# design.net
KiCad netlist of a schematic drawn in Altium Designer
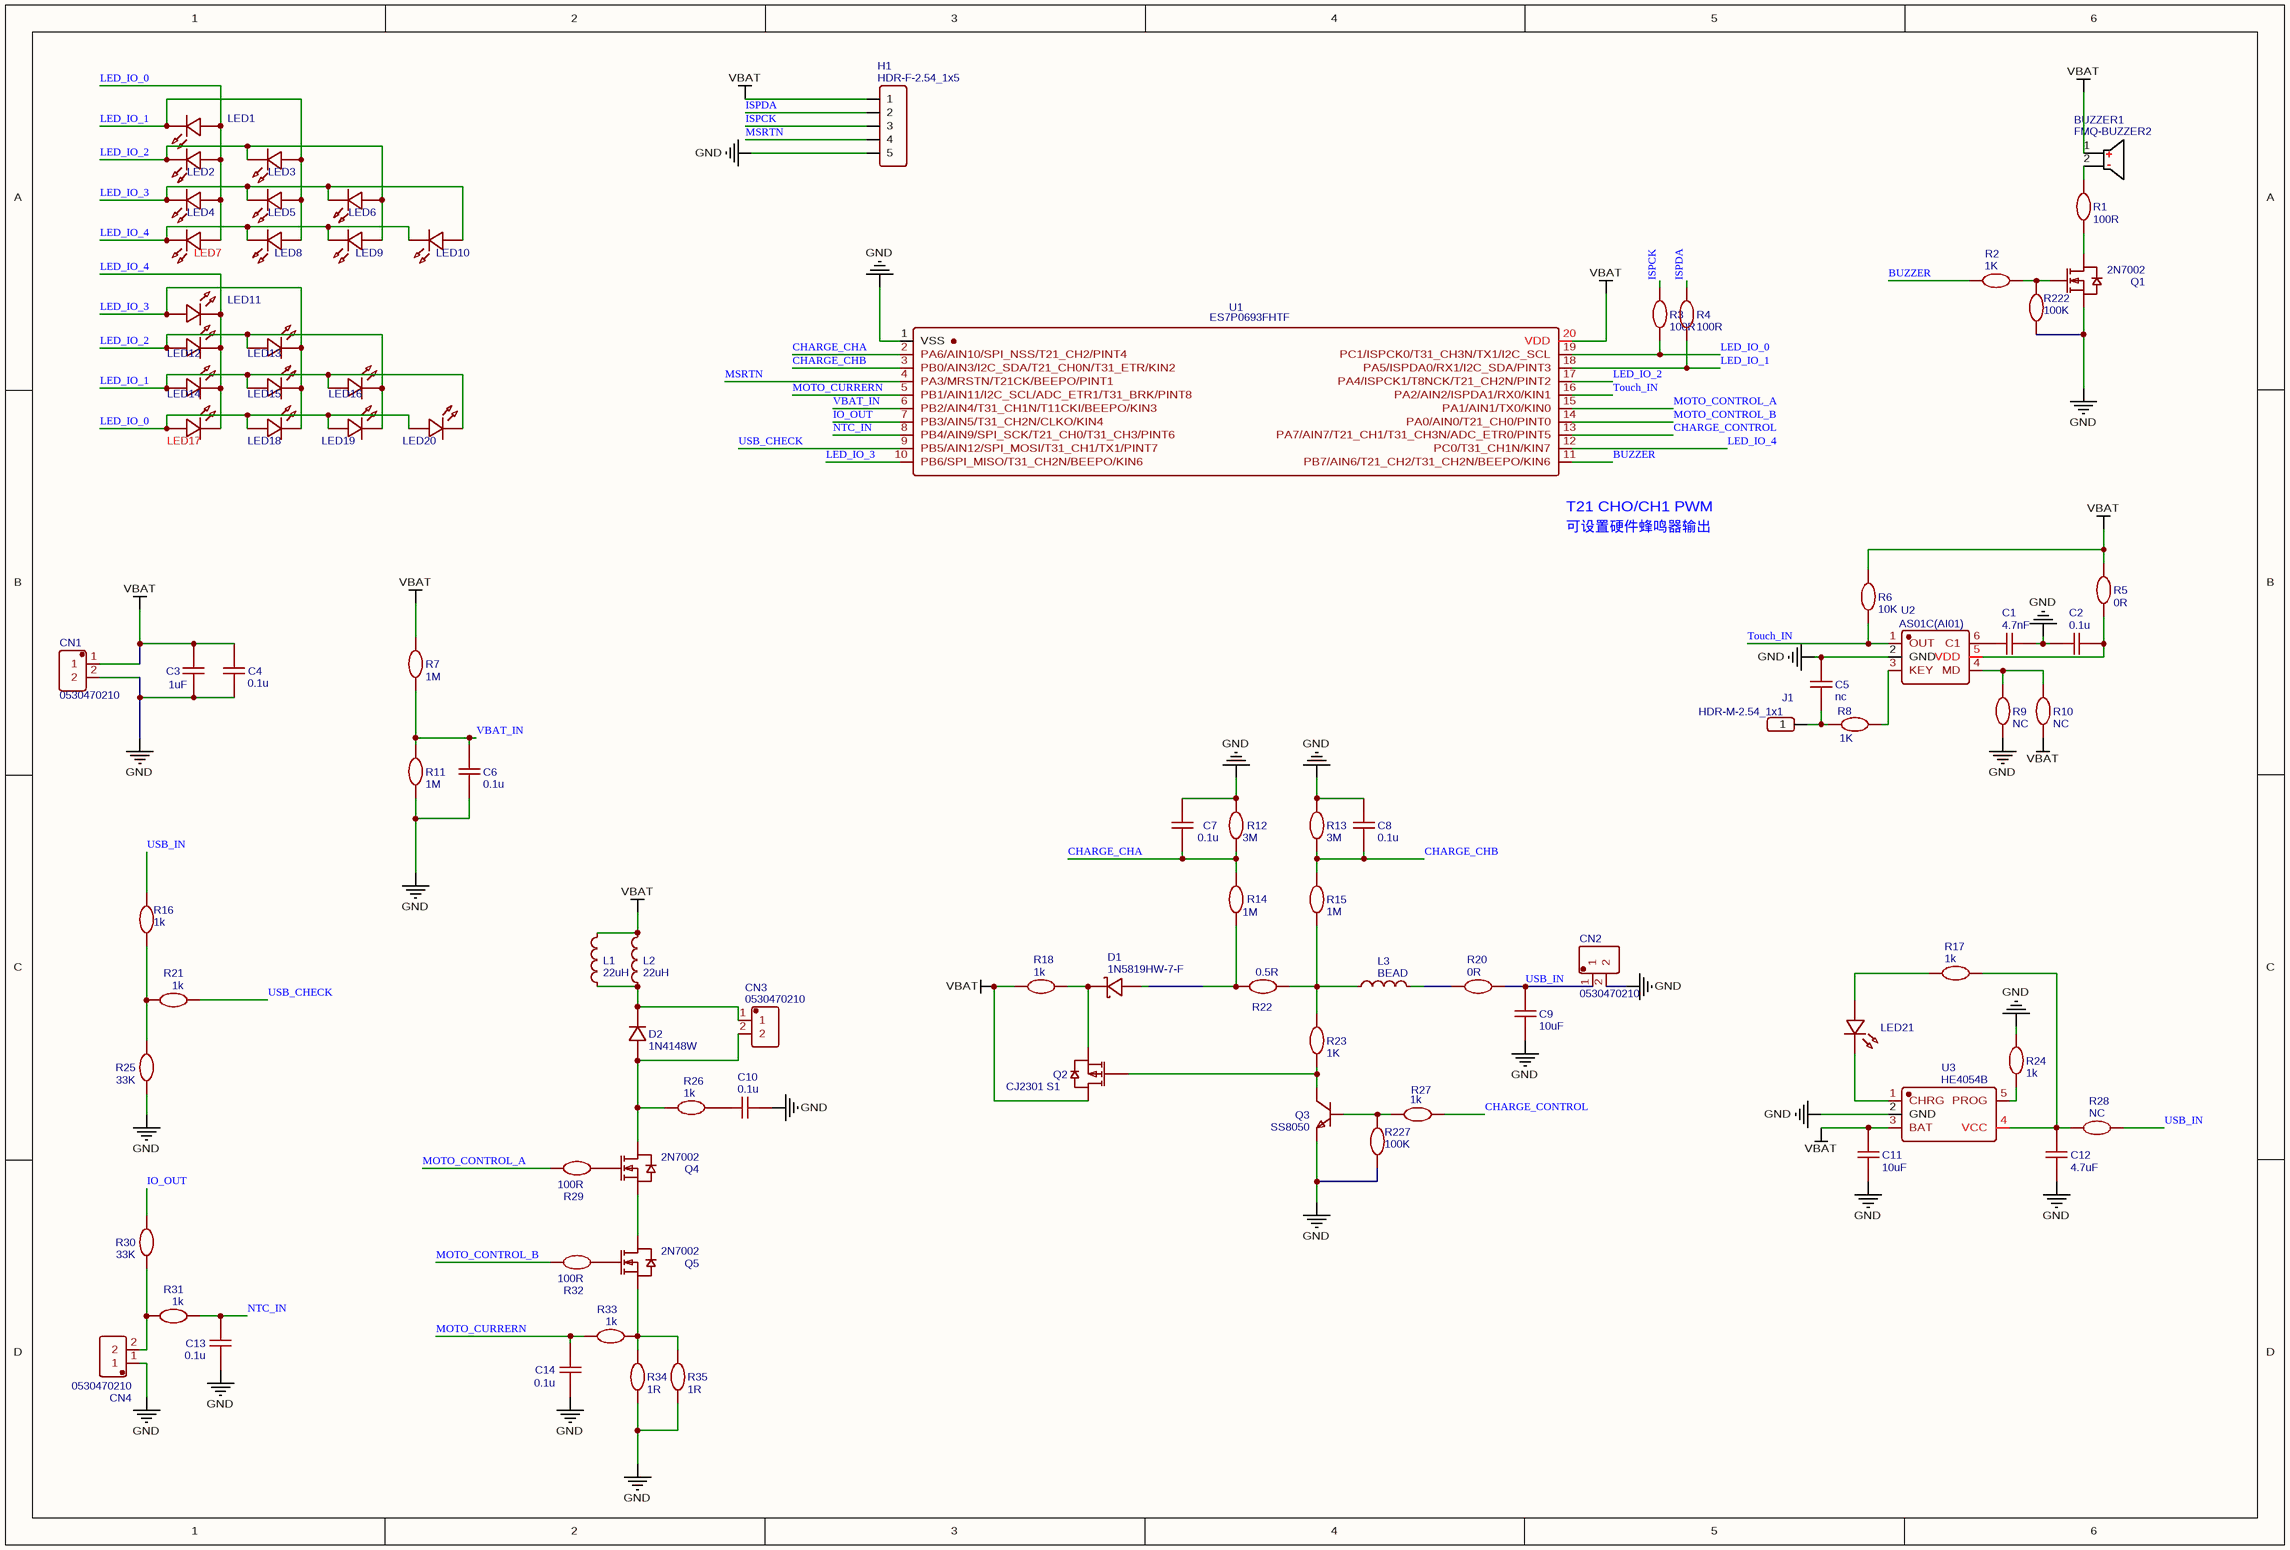
[diagram p0: 搅拌杯原理图.schdoc]

(export (version "E")
  (design (tool "Eeschema 10.0.6"))
  (components
    (comp (ref "BUZZER1")
      (value "FMQ-BUZZER2")
      (footprint "BUZ-TH_BD12.0-P7.60-D0.6-FD")
      (fields (field (name "BOM_SUPPLIER PART") "C9900006103") (field (name "CONTRIBUTOR") "LCSC"))
      (libsource (lib "altium-import") (part "root_0_FMQ-BUZZER2_"))
    )
    (comp (ref "C1")
      (value "4.7nF")
      (footprint "C0603")
      (fields (field (name "CONTRIBUTOR") "LCEDA_Lib"))
      (libsource (lib "altium-import") (part "root_0_4.7nF_"))
    )
    (comp (ref "C2")
      (value "0.1u")
      (footprint "C0603")
      (fields (field (name "CONTRIBUTOR") "LCEDA_Lib"))
      (libsource (lib "altium-import") (part "root_0_0.1u_"))
    )
    (comp (ref "C3")
      (value "1uF")
      (footprint "C0603")
      (fields (field (name "CONTRIBUTOR") "LCEDA_Lib"))
      (libsource (lib "altium-import") (part "root_3_1uF_"))
    )
    (comp (ref "C4")
      (value "0.1u")
      (footprint "C0603")
      (fields (field (name "CONTRIBUTOR") "LCEDA_Lib"))
      (libsource (lib "") (part "root_3_0.1u__1"))
    )
    (comp (ref "C5")
      (value "nc")
      (footprint "C0603")
      (fields (field (name "CONTRIBUTOR") "LCEDA_Lib"))
      (libsource (lib "altium-import") (part "root_1_nc_"))
    )
    (comp (ref "C6")
      (value "0.1u")
      (footprint "C0603")
      (fields (field (name "CONTRIBUTOR") "LCEDA_Lib"))
      (libsource (lib "altium-import") (part "root_1_0.1u_"))
    )
    (comp (ref "C7")
      (value "0.1u")
      (footprint "C0603")
      (fields (field (name "CONTRIBUTOR") "LCEDA_Lib"))
      (libsource (lib "altium-import") (part "root_3_0.1u_"))
    )
    (comp (ref "C8")
      (value "0.1u")
      (footprint "C0603")
      (fields (field (name "CONTRIBUTOR") "LCEDA_Lib"))
      (libsource (lib "altium-import") (part "root_1_0.1u_"))
    )
    (comp (ref "C9")
      (value "10uF")
      (footprint "C0603")
      (fields (field (name "CONTRIBUTOR") "LCEDA_Lib"))
      (libsource (lib "altium-import") (part "root_1_10uF_"))
    )
    (comp (ref "C10")
      (value "0.1u")
      (footprint "C0603")
      (fields (field (name "CONTRIBUTOR") "LCEDA_Lib"))
      (libsource (lib "altium-import") (part "root_2_0.1u_"))
    )
    (comp (ref "C11")
      (value "10uF")
      (footprint "C0603")
      (fields (field (name "CONTRIBUTOR") "LCEDA_Lib"))
      (libsource (lib "altium-import") (part "root_1_10uF_"))
    )
    (comp (ref "C12")
      (value "4.7uF")
      (footprint "C0603")
      (fields (field (name "CONTRIBUTOR") "LCEDA_Lib"))
      (libsource (lib "altium-import") (part "root_1_4.7uF_"))
    )
    (comp (ref "C13")
      (value "0.1u")
      (footprint "C0603")
      (fields (field (name "CONTRIBUTOR") "LCEDA_Lib"))
      (libsource (lib "altium-import") (part "root_3_0.1u_"))
    )
    (comp (ref "C14")
      (value "0.1u")
      (footprint "C0603")
      (fields (field (name "CONTRIBUTOR") "LCEDA_Lib"))
      (libsource (lib "") (part "root_1_0.1u__1"))
    )
    (comp (ref "CN1")
      (value "0530470210")
      (footprint "CONN-TH_0530470210")
      (fields (field (name "BOM_SUPPLIER PART") "C114130") (field (name "CONTRIBUTOR") "LCSC"))
      (libsource (lib "altium-import") (part "root_0_mirrored_0530470210_"))
    )
    (comp (ref "CN2")
      (value "0530470210")
      (footprint "CONN-TH_0530470210")
      (fields (field (name "BOM_SUPPLIER PART") "C114130") (field (name "CONTRIBUTOR") "LCSC"))
      (libsource (lib "altium-import") (part "root_1_mirrored_0530470210_"))
    )
    (comp (ref "CN3")
      (value "0530470210")
      (footprint "CONN-TH_0530470210")
      (fields (field (name "BOM_SUPPLIER PART") "C114130") (field (name "CONTRIBUTOR") "LCSC"))
      (libsource (lib "altium-import") (part "root_0_0530470210_"))
    )
    (comp (ref "CN4")
      (value "0530470210")
      (footprint "CONN-TH_0530470210")
      (fields (field (name "BOM_SUPPLIER PART") "C114130") (field (name "CONTRIBUTOR") "LCSC"))
      (libsource (lib "") (part "root_0_0530470210__1"))
    )
    (comp (ref "D1")
      (value "1N5819HW-7-F")
      (footprint "SOD-123_L2.8-W1.8-LS3.7-FD")
      (fields (field (name "BOM_SUPPLIER PART") "C82544"))
      (libsource (lib "altium-import") (part "root_2_1N5819HW-7-F_"))
    )
    (comp (ref "D2")
      (value "1N4148W")
      (footprint "SOD-123FL_L2.6-W1.6-LS3.4-RD")
      (fields (field (name "BOM_SUPPLIER PART") "C129216") (field (name "CONTRIBUTOR") "LCEDA_Lib"))
      (libsource (lib "altium-import") (part "root_1_1N4148W_"))
    )
    (comp (ref "H1")
      (value "HDR-F-2.54_1x5")
      (footprint "1.27mm_5PIN")
      (fields (field (name "BOM_SUPPLIER PART") "C50950") (field (name "CONTRIBUTOR") "LCEDA_Lib"))
      (libsource (lib "altium-import") (part "root_0_HDR-F-2.54_1x5_"))
    )
    (comp (ref "J1")
      (value "HDR-M-2.54_1x1")
      (footprint "HDR-M-2.54_1X1")
      (fields (field (name "BOM_SUPPLIER PART") "C81276") (field (name "CONTRIBUTOR") "LCEDA_Lib"))
      (libsource (lib "altium-import") (part "root_2_HDR-M-2.54_1x1_"))
    )
    (comp (ref "L1")
      (value "22uH")
      (footprint "L0603")
      (fields (field (name "CONTRIBUTOR") "LCEDA_Lib"))
      (libsource (lib "altium-import") (part "root_1_22uH_"))
    )
    (comp (ref "L2")
      (value "22uH")
      (footprint "L0603")
      (fields (field (name "CONTRIBUTOR") "LCEDA_Lib"))
      (libsource (lib "altium-import") (part "root_1_22uH_"))
    )
    (comp (ref "L3")
      (value "BEAD")
      (footprint "L0603")
      (fields (field (name "CONTRIBUTOR") "LCEDA_Lib"))
      (libsource (lib "altium-import") (part "root_0_22uH_"))
    )
    (comp (ref "LED1")
      (value "LED-0603_W")
      (footprint "LED0603-FD_WHITE")
      (fields
        (field (name "BOM_MANUFACTURER PART") "17-21SURC/S530-A3/TR8")
        (field (name "BOM_SUPPLIER PART") "C72037")
        (field (name "CONTRIBUTOR") "LCEDA_Lib")
      )
      (libsource (lib "altium-import") (part "root_2_LED-0603_W_"))
    )
    (comp (ref "LED2")
      (value "LED-0603_W")
      (footprint "LED0603-FD_WHITE")
      (fields
        (field (name "BOM_MANUFACTURER PART") "17-21SURC/S530-A3/TR8")
        (field (name "BOM_SUPPLIER PART") "C72037")
        (field (name "CONTRIBUTOR") "LCEDA_Lib")
      )
      (libsource (lib "altium-import") (part "root_2_LED-0603_W_"))
    )
    (comp (ref "LED3")
      (value "LED-0603_W")
      (footprint "LED0603-FD_WHITE")
      (fields
        (field (name "BOM_MANUFACTURER PART") "17-21SURC/S530-A3/TR8")
        (field (name "BOM_SUPPLIER PART") "C72037")
        (field (name "CONTRIBUTOR") "LCEDA_Lib")
      )
      (libsource (lib "altium-import") (part "root_2_LED-0603_W_"))
    )
    (comp (ref "LED4")
      (value "LED-0603_W")
      (footprint "LED0603-FD_WHITE")
      (fields
        (field (name "BOM_MANUFACTURER PART") "17-21SURC/S530-A3/TR8")
        (field (name "BOM_SUPPLIER PART") "C72037")
        (field (name "CONTRIBUTOR") "LCEDA_Lib")
      )
      (libsource (lib "altium-import") (part "root_2_LED-0603_W_"))
    )
    (comp (ref "LED5")
      (value "LED-0603_W")
      (footprint "LED0603-FD_WHITE")
      (fields
        (field (name "BOM_MANUFACTURER PART") "17-21SURC/S530-A3/TR8")
        (field (name "BOM_SUPPLIER PART") "C72037")
        (field (name "CONTRIBUTOR") "LCEDA_Lib")
      )
      (libsource (lib "altium-import") (part "root_2_LED-0603_W_"))
    )
    (comp (ref "LED6")
      (value "LED-0603_W")
      (footprint "LED0603-FD_WHITE")
      (fields
        (field (name "BOM_MANUFACTURER PART") "17-21SURC/S530-A3/TR8")
        (field (name "BOM_SUPPLIER PART") "C72037")
        (field (name "CONTRIBUTOR") "LCEDA_Lib")
      )
      (libsource (lib "altium-import") (part "root_2_LED-0603_W_"))
    )
    (comp (ref "LED7")
      (value "LED-0603_W")
      (footprint "LED0603-FD_WHITE")
      (fields
        (field (name "BOM_MANUFACTURER PART") "17-21SURC/S530-A3/TR8")
        (field (name "BOM_SUPPLIER PART") "C72037")
        (field (name "CONTRIBUTOR") "LCEDA_Lib")
      )
      (libsource (lib "altium-import") (part "root_2_LED-0603_W_"))
    )
    (comp (ref "LED8")
      (value "LED-0603_W")
      (footprint "LED0603-FD_WHITE")
      (fields
        (field (name "BOM_MANUFACTURER PART") "17-21SURC/S530-A3/TR8")
        (field (name "BOM_SUPPLIER PART") "C72037")
        (field (name "CONTRIBUTOR") "LCEDA_Lib")
      )
      (libsource (lib "altium-import") (part "root_2_LED-0603_W_"))
    )
    (comp (ref "LED9")
      (value "LED-0603_W")
      (footprint "LED0603-FD_WHITE")
      (fields
        (field (name "BOM_MANUFACTURER PART") "17-21SURC/S530-A3/TR8")
        (field (name "BOM_SUPPLIER PART") "C72037")
        (field (name "CONTRIBUTOR") "LCEDA_Lib")
      )
      (libsource (lib "altium-import") (part "root_2_LED-0603_W_"))
    )
    (comp (ref "LED10")
      (value "LED-0603_W")
      (footprint "LED0603-FD_WHITE")
      (fields
        (field (name "BOM_MANUFACTURER PART") "17-21SURC/S530-A3/TR8")
        (field (name "BOM_SUPPLIER PART") "C72037")
        (field (name "CONTRIBUTOR") "LCEDA_Lib")
      )
      (libsource (lib "altium-import") (part "root_2_LED-0603_W_"))
    )
    (comp (ref "LED11")
      (value "LED-0603_W")
      (footprint "LED0603-FD_WHITE")
      (fields
        (field (name "BOM_MANUFACTURER PART") "17-21SURC/S530-A3/TR8")
        (field (name "BOM_SUPPLIER PART") "C72037")
        (field (name "CONTRIBUTOR") "LCEDA_Lib")
      )
      (libsource (lib "altium-import") (part "root_0_LED-0603_W_"))
    )
    (comp (ref "LED12")
      (value "LED-0603_W")
      (footprint "LED0603-FD_WHITE")
      (fields
        (field (name "BOM_MANUFACTURER PART") "17-21SURC/S530-A3/TR8")
        (field (name "BOM_SUPPLIER PART") "C72037")
        (field (name "CONTRIBUTOR") "LCEDA_Lib")
      )
      (libsource (lib "altium-import") (part "root_0_LED-0603_W_"))
    )
    (comp (ref "LED13")
      (value "LED-0603_W")
      (footprint "LED0603-FD_WHITE")
      (fields
        (field (name "BOM_MANUFACTURER PART") "17-21SURC/S530-A3/TR8")
        (field (name "BOM_SUPPLIER PART") "C72037")
        (field (name "CONTRIBUTOR") "LCEDA_Lib")
      )
      (libsource (lib "altium-import") (part "root_0_LED-0603_W_"))
    )
    (comp (ref "LED14")
      (value "LED-0603_W")
      (footprint "LED0603-FD_WHITE")
      (fields
        (field (name "BOM_MANUFACTURER PART") "17-21SURC/S530-A3/TR8")
        (field (name "BOM_SUPPLIER PART") "C72037")
        (field (name "CONTRIBUTOR") "LCEDA_Lib")
      )
      (libsource (lib "altium-import") (part "root_0_LED-0603_W_"))
    )
    (comp (ref "LED15")
      (value "LED-0603_W")
      (footprint "LED0603-FD_WHITE")
      (fields
        (field (name "BOM_MANUFACTURER PART") "17-21SURC/S530-A3/TR8")
        (field (name "BOM_SUPPLIER PART") "C72037")
        (field (name "CONTRIBUTOR") "LCEDA_Lib")
      )
      (libsource (lib "altium-import") (part "root_0_LED-0603_W_"))
    )
    (comp (ref "LED16")
      (value "LED-0603_W")
      (footprint "LED0603-FD_WHITE")
      (fields
        (field (name "BOM_MANUFACTURER PART") "17-21SURC/S530-A3/TR8")
        (field (name "BOM_SUPPLIER PART") "C72037")
        (field (name "CONTRIBUTOR") "LCEDA_Lib")
      )
      (libsource (lib "altium-import") (part "root_0_LED-0603_W_"))
    )
    (comp (ref "LED17")
      (value "LED-0603_W")
      (footprint "LED0603-FD_WHITE")
      (fields
        (field (name "BOM_MANUFACTURER PART") "17-21SURC/S530-A3/TR8")
        (field (name "BOM_SUPPLIER PART") "C72037")
        (field (name "CONTRIBUTOR") "LCEDA_Lib")
      )
      (libsource (lib "altium-import") (part "root_0_LED-0603_W_"))
    )
    (comp (ref "LED18")
      (value "LED-0603_W")
      (footprint "LED0603-FD_WHITE")
      (fields
        (field (name "BOM_MANUFACTURER PART") "17-21SURC/S530-A3/TR8")
        (field (name "BOM_SUPPLIER PART") "C72037")
        (field (name "CONTRIBUTOR") "LCEDA_Lib")
      )
      (libsource (lib "altium-import") (part "root_0_LED-0603_W_"))
    )
    (comp (ref "LED19")
      (value "LED-0603_W")
      (footprint "LED0603-FD_WHITE")
      (fields
        (field (name "BOM_MANUFACTURER PART") "17-21SURC/S530-A3/TR8")
        (field (name "BOM_SUPPLIER PART") "C72037")
        (field (name "CONTRIBUTOR") "LCEDA_Lib")
      )
      (libsource (lib "altium-import") (part "root_0_LED-0603_W_"))
    )
    (comp (ref "LED20")
      (value "LED-0603_W")
      (footprint "LED0603-FD_WHITE")
      (fields
        (field (name "BOM_MANUFACTURER PART") "17-21SURC/S530-A3/TR8")
        (field (name "BOM_SUPPLIER PART") "C72037")
        (field (name "CONTRIBUTOR") "LCEDA_Lib")
      )
      (libsource (lib "altium-import") (part "root_0_LED-0603_W_"))
    )
    (comp (ref "LED21")
      (value "LED-0603_W")
      (footprint "LED0603-FD_WHITE")
      (fields
        (field (name "BOM_MANUFACTURER PART") "17-21SURC/S530-A3/TR8")
        (field (name "BOM_SUPPLIER PART") "C72037")
        (field (name "CONTRIBUTOR") "LCEDA_Lib")
      )
      (libsource (lib "altium-import") (part "root_3_LED-0603_W_"))
    )
    (comp (ref "Q1")
      (value "2N7002")
      (footprint "SOT-23_L2.9-W1.3-P0.95-LS2.4-BR")
      (fields
        (field (name "BOM_MANUFACTURER PART") "2N7002,215")
        (field (name "BOM_SUPPLIER PART") "C65189")
        (field (name "CONTRIBUTOR") "LCEDA_Lib")
      )
      (libsource (lib "altium-import") (part "root_2_2N7002_"))
    )
    (comp (ref "Q2")
      (value "CJ2301 S1")
      (footprint "SOT-23-3_L3.0-W1.7-P0.95-LS2.9-BR")
      (fields (field (name "BOM_SUPPLIER PART") "C8547"))
      (libsource (lib "altium-import") (part "root_2_CJ2301 S1_"))
    )
    (comp (ref "Q3")
      (value "SS8050")
      (footprint "SOT-23-3_L2.9-W1.3-P1.90-LS2.4-BR")
      (fields (field (name "BOM_SUPPLIER PART") "C908250") (field (name "CONTRIBUTOR") "LCSC"))
      (libsource (lib "altium-import") (part "root_0_SS8050_"))
    )
    (comp (ref "Q4")
      (value "2N7002")
      (footprint "SOT-23_L2.9-W1.3-P0.95-LS2.4-BR")
      (fields
        (field (name "BOM_MANUFACTURER PART") "2N7002,215")
        (field (name "BOM_SUPPLIER PART") "C65189")
        (field (name "CONTRIBUTOR") "LCEDA_Lib")
      )
      (libsource (lib "altium-import") (part "root_2_2N7002_"))
    )
    (comp (ref "Q5")
      (value "2N7002")
      (footprint "SOT-23_L2.9-W1.3-P0.95-LS2.4-BR")
      (fields
        (field (name "BOM_MANUFACTURER PART") "2N7002,215")
        (field (name "BOM_SUPPLIER PART") "C65189")
        (field (name "CONTRIBUTOR") "LCEDA_Lib")
      )
      (libsource (lib "altium-import") (part "root_2_2N7002_"))
    )
    (comp (ref "R1")
      (value "100R")
      (footprint "R0603")
      (fields (field (name "CONTRIBUTOR") "LCEDA_Lib"))
      (libsource (lib "altium-import") (part "root_3_100R_"))
    )
    (comp (ref "R2")
      (value "1K")
      (footprint "R0603")
      (fields (field (name "CONTRIBUTOR") "LCEDA_Lib"))
      (libsource (lib "altium-import") (part "root_2_1K_"))
    )
    (comp (ref "R3")
      (value "100R")
      (footprint "R0603")
      (fields (field (name "CONTRIBUTOR") "LCEDA_Lib"))
      (libsource (lib "altium-import") (part "root_3_100R_"))
    )
    (comp (ref "R4")
      (value "100R")
      (footprint "R0603")
      (fields (field (name "CONTRIBUTOR") "LCEDA_Lib"))
      (libsource (lib "altium-import") (part "root_3_100R_"))
    )
    (comp (ref "R5")
      (value "0R")
      (footprint "R0603")
      (fields (field (name "CONTRIBUTOR") "LCEDA_Lib"))
      (libsource (lib "altium-import") (part "root_1_NC_"))
    )
    (comp (ref "R6")
      (value "10K")
      (footprint "R0603")
      (fields (field (name "CONTRIBUTOR") "LCEDA_Lib"))
      (libsource (lib "altium-import") (part "root_1_NC_"))
    )
    (comp (ref "R7")
      (value "1M")
      (footprint "R0603")
      (fields (field (name "CONTRIBUTOR") "LCEDA_Lib"))
      (libsource (lib "altium-import") (part "root_1_430k_"))
    )
    (comp (ref "R8")
      (value "1K")
      (footprint "R0603")
      (fields (field (name "CONTRIBUTOR") "LCEDA_Lib"))
      (libsource (lib "altium-import") (part "root_2_1K_"))
    )
    (comp (ref "R9")
      (value "NC")
      (footprint "R0603")
      (fields (field (name "CONTRIBUTOR") "LCEDA_Lib"))
      (libsource (lib "altium-import") (part "root_1_NC_"))
    )
    (comp (ref "R10")
      (value "NC")
      (footprint "R0603")
      (fields (field (name "CONTRIBUTOR") "LCEDA_Lib"))
      (libsource (lib "altium-import") (part "root_1_NC_"))
    )
    (comp (ref "R11")
      (value "1M")
      (footprint "R0603")
      (fields (field (name "CONTRIBUTOR") "LCEDA_Lib"))
      (libsource (lib "altium-import") (part "root_1_430K_"))
    )
    (comp (ref "R12")
      (value "3M")
      (footprint "R0603")
      (fields (field (name "CONTRIBUTOR") "LCEDA_Lib"))
      (libsource (lib "") (part "root_3_1k__1"))
    )
    (comp (ref "R13")
      (value "3M")
      (footprint "R0603")
      (fields (field (name "CONTRIBUTOR") "LCEDA_Lib"))
      (libsource (lib "altium-import") (part "root_1_1k_"))
    )
    (comp (ref "R14")
      (value "1M")
      (footprint "R0603")
      (fields (field (name "CONTRIBUTOR") "LCEDA_Lib"))
      (libsource (lib "altium-import") (part "root_3_1k_"))
    )
    (comp (ref "R15")
      (value "1M")
      (footprint "R0603")
      (fields (field (name "CONTRIBUTOR") "LCEDA_Lib"))
      (libsource (lib "altium-import") (part "root_1_1k_"))
    )
    (comp (ref "R16")
      (value "1k")
      (footprint "R0603")
      (fields (field (name "CONTRIBUTOR") "LCEDA_Lib"))
      (libsource (lib "altium-import") (part "root_3_1k_"))
    )
    (comp (ref "R17")
      (value "1k")
      (footprint "R0603")
      (fields (field (name "CONTRIBUTOR") "LCEDA_Lib"))
      (libsource (lib "altium-import") (part "root_2_1k_"))
    )
    (comp (ref "R18")
      (value "1k")
      (footprint "R0603")
      (fields (field (name "CONTRIBUTOR") "LCEDA_Lib"))
      (libsource (lib "altium-import") (part "root_2_1k_"))
    )
    (comp (ref "R20")
      (value "0R")
      (footprint "R0603")
      (fields (field (name "CONTRIBUTOR") "LCEDA_Lib"))
      (libsource (lib "altium-import") (part "root_2_NC_"))
    )
    (comp (ref "R21")
      (value "1k")
      (footprint "R0603")
      (fields (field (name "CONTRIBUTOR") "LCEDA_Lib"))
      (libsource (lib "") (part "root_2_1k__1"))
    )
    (comp (ref "R22")
      (value "0.5R")
      (footprint "R1206")
      (fields (field (name "CONTRIBUTOR") "LCEDA_Lib"))
      (libsource (lib "altium-import") (part "root_0_0.5R_"))
    )
    (comp (ref "R23")
      (value "1K")
      (footprint "R0603")
      (fields (field (name "CONTRIBUTOR") "LCEDA_Lib"))
      (libsource (lib "altium-import") (part "root_1_1k_"))
    )
    (comp (ref "R24")
      (value "1k")
      (footprint "R0603")
      (fields (field (name "CONTRIBUTOR") "LCEDA_Lib"))
      (libsource (lib "altium-import") (part "root_1_1k_"))
    )
    (comp (ref "R25")
      (value "33K")
      (footprint "R0603")
      (fields (field (name "CONTRIBUTOR") "LCEDA_Lib"))
      (libsource (lib "altium-import") (part "root_3_33K_"))
    )
    (comp (ref "R26")
      (value "1k")
      (footprint "R0603")
      (fields (field (name "CONTRIBUTOR") "LCEDA_Lib"))
      (libsource (lib "altium-import") (part "root_2_1k_"))
    )
    (comp (ref "R27")
      (value "1k")
      (footprint "R0603")
      (fields (field (name "CONTRIBUTOR") "LCEDA_Lib"))
      (libsource (lib "") (part "root_0_1k__1"))
    )
    (comp (ref "R28")
      (value "NC")
      (footprint "R0603")
      (fields (field (name "CONTRIBUTOR") "LCEDA_Lib"))
      (libsource (lib "altium-import") (part "root_0_NC_"))
    )
    (comp (ref "R29")
      (value "100R")
      (footprint "R0603")
      (fields (field (name "CONTRIBUTOR") "LCEDA_Lib"))
      (libsource (lib "altium-import") (part "root_2_100R_"))
    )
    (comp (ref "R30")
      (value "33K")
      (footprint "R0603")
      (fields (field (name "CONTRIBUTOR") "LCEDA_Lib"))
      (libsource (lib "altium-import") (part "root_3_33K_"))
    )
    (comp (ref "R31")
      (value "1k")
      (footprint "R0603")
      (fields (field (name "CONTRIBUTOR") "LCEDA_Lib"))
      (libsource (lib "") (part "root_2_1k__1"))
    )
    (comp (ref "R32")
      (value "100R")
      (footprint "R0603")
      (fields (field (name "CONTRIBUTOR") "LCEDA_Lib"))
      (libsource (lib "altium-import") (part "root_2_100R_"))
    )
    (comp (ref "R33")
      (value "1k")
      (footprint "R0603")
      (fields (field (name "CONTRIBUTOR") "LCEDA_Lib"))
      (libsource (lib "altium-import") (part "root_0_1k_"))
    )
    (comp (ref "R34")
      (value "1R")
      (footprint "R1206")
      (fields (field (name "CONTRIBUTOR") "LCEDA_Lib"))
      (libsource (lib "altium-import") (part "root_1_1R_"))
    )
    (comp (ref "R35")
      (value "1R")
      (footprint "R1206")
      (fields (field (name "CONTRIBUTOR") "LCEDA_Lib"))
      (libsource (lib "altium-import") (part "root_1_1R_"))
    )
    (comp (ref "R222")
      (value "100K")
      (footprint "R0603")
      (fields (field (name "CONTRIBUTOR") "LCEDA_Lib"))
      (libsource (lib "altium-import") (part "root_3_1K_"))
    )
    (comp (ref "R227")
      (value "100K")
      (footprint "R0603")
      (fields (field (name "CONTRIBUTOR") "LCEDA_Lib"))
      (libsource (lib "altium-import") (part "root_3_1K_"))
    )
    (comp (ref "U1")
      (value "ES7P0693FHTF")
      (footprint "TSOP20")
      (fields (field (name "CONTRIBUTOR") "zime_zl"))
      (libsource (lib "altium-import") (part "root_0_ES7P0693FHTF_"))
    )
    (comp (ref "U2")
      (value "AS01C(AI01)")
      (footprint "SOT-23-6_L2.9-W1.6-P0.95-LS2.8-BL")
      (fields (field (name "BOM_SUPPLIER PART") "C389617") (field (name "CONTRIBUTOR") "LCSC"))
      (libsource (lib "altium-import") (part "root_0_AS01C(AI01)_"))
    )
    (comp (ref "U3")
      (value "HE4054B")
      (footprint "SOT-23-5_L3.0-W1.7-P0.95-LS2.8-BR")
      (fields (field (name "BOM_SUPPLIER PART") "C711953") (field (name "CONTRIBUTOR") "LCSC"))
      (libsource (lib "altium-import") (part "root_0_HE4054B_"))
    )
  )
  (nets
    (net (code "1") (name "/BUZZER") (class "Default")
      (node (ref "R2") (pin "2") (pinfunction "2_2") (pintype "passive"))
      (node (ref "U1") (pin "11") (pinfunction "PB7/AIN6/T21_CH2/T31_CH2N/BEEPO/KIN6_11") (pintype "passive"))
    )
    (net (code "2") (name "/CHARGE_CHA") (class "Default")
      (node (ref "C7") (pin "2") (pinfunction "2_2") (pintype "passive"))
      (node (ref "R12") (pin "2") (pinfunction "2_2") (pintype "passive"))
      (node (ref "R14") (pin "2") (pinfunction "2_2") (pintype "passive"))
      (node (ref "U1") (pin "2") (pinfunction "PA6/AIN10/SPI_NSS/T21_CH2/PINT4_2") (pintype "passive"))
    )
    (net (code "3") (name "/CHARGE_CHB") (class "Default")
      (node (ref "C8") (pin "1") (pinfunction "1_1") (pintype "passive"))
      (node (ref "R13") (pin "1") (pinfunction "1_1") (pintype "passive"))
      (node (ref "R15") (pin "2") (pinfunction "2_2") (pintype "passive"))
      (node (ref "U1") (pin "3") (pinfunction "PB0/AIN3/I2C_SDA/T21_CH0N/T31_ETR/KIN2_3") (pintype "passive"))
    )
    (net (code "4") (name "/CHARGE_CONTROL") (class "Default")
      (node (ref "R27") (pin "2") (pinfunction "2_2") (pintype "passive"))
      (node (ref "U1") (pin "13") (pinfunction "PA7/AIN7/T21_CH1/T31_CH3N/ADC_ETR0/PINT5_13") (pintype "passive"))
    )
    (net (code "5") (name "/IO_OUT") (class "Default")
      (node (ref "R30") (pin "1") (pinfunction "1_1") (pintype "passive"))
      (node (ref "U1") (pin "7") (pinfunction "PB3/AIN5/T31_CH2N/CLKO/KIN4_7") (pintype "passive"))
    )
    (net (code "6") (name "/ISPCK") (class "Default")
      (node (ref "H1") (pin "3") (pinfunction "3_3") (pintype "passive"))
      (node (ref "R3") (pin "1") (pinfunction "1_1") (pintype "passive"))
    )
    (net (code "7") (name "/ISPDA") (class "Default")
      (node (ref "H1") (pin "2") (pinfunction "2_2") (pintype "passive"))
      (node (ref "R4") (pin "1") (pinfunction "1_1") (pintype "passive"))
    )
    (net (code "8") (name "/LED_IO_0") (class "Default")
      (node (ref "LED1") (pin "1") (pinfunction "1_1") (pintype "passive"))
      (node (ref "LED17") (pin "1") (pinfunction "1_1") (pintype "passive"))
      (node (ref "LED18") (pin "1") (pinfunction "1_1") (pintype "passive"))
      (node (ref "LED19") (pin "1") (pinfunction "1_1") (pintype "passive"))
      (node (ref "LED2") (pin "1") (pinfunction "1_1") (pintype "passive"))
      (node (ref "LED20") (pin "1") (pinfunction "1_1") (pintype "passive"))
      (node (ref "LED4") (pin "1") (pinfunction "1_1") (pintype "passive"))
      (node (ref "LED7") (pin "1") (pinfunction "1_1") (pintype "passive"))
      (node (ref "R3") (pin "2") (pinfunction "2_2") (pintype "passive"))
      (node (ref "U1") (pin "19") (pinfunction "PC1/ISPCK0/T31_CH3N/TX1/I2C_SCL_19") (pintype "passive"))
    )
    (net (code "9") (name "/LED_IO_1") (class "Default")
      (node (ref "LED1") (pin "2") (pinfunction "2_2") (pintype "passive"))
      (node (ref "LED14") (pin "1") (pinfunction "1_1") (pintype "passive"))
      (node (ref "LED15") (pin "1") (pinfunction "1_1") (pintype "passive"))
      (node (ref "LED16") (pin "1") (pinfunction "1_1") (pintype "passive"))
      (node (ref "LED20") (pin "2") (pinfunction "2_2") (pintype "passive"))
      (node (ref "LED3") (pin "1") (pinfunction "1_1") (pintype "passive"))
      (node (ref "LED5") (pin "1") (pinfunction "1_1") (pintype "passive"))
      (node (ref "LED8") (pin "1") (pinfunction "1_1") (pintype "passive"))
      (node (ref "R4") (pin "2") (pinfunction "2_2") (pintype "passive"))
      (node (ref "U1") (pin "18") (pinfunction "PA5/ISPDA0/RX1/I2C_SDA/PINT3_18") (pintype "passive"))
    )
    (net (code "10") (name "/LED_IO_2") (class "Default")
      (node (ref "LED12") (pin "1") (pinfunction "1_1") (pintype "passive"))
      (node (ref "LED13") (pin "1") (pinfunction "1_1") (pintype "passive"))
      (node (ref "LED16") (pin "2") (pinfunction "2_2") (pintype "passive"))
      (node (ref "LED19") (pin "2") (pinfunction "2_2") (pintype "passive"))
      (node (ref "LED2") (pin "2") (pinfunction "2_2") (pintype "passive"))
      (node (ref "LED3") (pin "2") (pinfunction "2_2") (pintype "passive"))
      (node (ref "LED6") (pin "1") (pinfunction "1_1") (pintype "passive"))
      (node (ref "LED9") (pin "1") (pinfunction "1_1") (pintype "passive"))
      (node (ref "U1") (pin "17") (pinfunction "PA4/ISPCK1/T8NCK/T21_CH2N/PINT2_17") (pintype "passive"))
    )
    (net (code "11") (name "/LED_IO_3") (class "Default")
      (node (ref "LED10") (pin "1") (pinfunction "1_1") (pintype "passive"))
      (node (ref "LED11") (pin "1") (pinfunction "1_1") (pintype "passive"))
      (node (ref "LED13") (pin "2") (pinfunction "2_2") (pintype "passive"))
      (node (ref "LED15") (pin "2") (pinfunction "2_2") (pintype "passive"))
      (node (ref "LED18") (pin "2") (pinfunction "2_2") (pintype "passive"))
      (node (ref "LED4") (pin "2") (pinfunction "2_2") (pintype "passive"))
      (node (ref "LED5") (pin "2") (pinfunction "2_2") (pintype "passive"))
      (node (ref "LED6") (pin "2") (pinfunction "2_2") (pintype "passive"))
      (node (ref "U1") (pin "10") (pinfunction "PB6/SPI_MISO/T31_CH2N/BEEPO/KIN6_10") (pintype "passive"))
    )
    (net (code "12") (name "/LED_IO_4") (class "Default")
      (node (ref "LED10") (pin "2") (pinfunction "2_2") (pintype "passive"))
      (node (ref "LED11") (pin "2") (pinfunction "2_2") (pintype "passive"))
      (node (ref "LED12") (pin "2") (pinfunction "2_2") (pintype "passive"))
      (node (ref "LED14") (pin "2") (pinfunction "2_2") (pintype "passive"))
      (node (ref "LED17") (pin "2") (pinfunction "2_2") (pintype "passive"))
      (node (ref "LED7") (pin "2") (pinfunction "2_2") (pintype "passive"))
      (node (ref "LED8") (pin "2") (pinfunction "2_2") (pintype "passive"))
      (node (ref "LED9") (pin "2") (pinfunction "2_2") (pintype "passive"))
      (node (ref "U1") (pin "12") (pinfunction "PC0/T31_CH1N/KIN7_12") (pintype "passive"))
    )
    (net (code "13") (name "/MOTO_CONTROL_A") (class "Default")
      (node (ref "R29") (pin "1") (pinfunction "1_1") (pintype "passive"))
      (node (ref "U1") (pin "15") (pinfunction "PA1/AIN1/TX0/KIN0_15") (pintype "passive"))
    )
    (net (code "14") (name "/MOTO_CONTROL_B") (class "Default")
      (node (ref "R32") (pin "1") (pinfunction "1_1") (pintype "passive"))
      (node (ref "U1") (pin "14") (pinfunction "PA0/AIN0/T21_CH0/PINT0_14") (pintype "passive"))
    )
    (net (code "15") (name "/MOTO_CURRERN") (class "Default")
      (node (ref "C14") (pin "2") (pinfunction "2_2") (pintype "passive"))
      (node (ref "R33") (pin "2") (pinfunction "2_2") (pintype "passive"))
      (node (ref "U1") (pin "5") (pinfunction "PB1/AIN11/I2C_SCL/ADC_ETR1/T31_BRK/PINT8_5") (pintype "passive"))
    )
    (net (code "16") (name "/MSRTN") (class "Default")
      (node (ref "H1") (pin "4") (pinfunction "4_4") (pintype "passive"))
      (node (ref "U1") (pin "4") (pinfunction "PA3/MRSTN/T21CK/BEEPO/PINT1_4") (pintype "passive"))
    )
    (net (code "17") (name "/NTC_IN") (class "Default")
      (node (ref "C13") (pin "1") (pinfunction "1_1") (pintype "passive"))
      (node (ref "R31") (pin "2") (pinfunction "2_2") (pintype "passive"))
      (node (ref "U1") (pin "8") (pinfunction "PB4/AIN9/SPI_SCK/T21_CH0/T31_CH3/PINT6_8") (pintype "passive"))
    )
    (net (code "18") (name "/Touch_IN") (class "Default")
      (node (ref "R6") (pin "1") (pinfunction "1_1") (pintype "passive"))
      (node (ref "U1") (pin "16") (pinfunction "PA2/AIN2/ISPDA1/RX0/KIN1_16") (pintype "passive"))
      (node (ref "U2") (pin "1") (pinfunction "OUT_1") (pintype "passive"))
    )
    (net (code "19") (name "/USB_CHECK") (class "Default")
      (node (ref "R21") (pin "2") (pinfunction "2_2") (pintype "passive"))
      (node (ref "U1") (pin "9") (pinfunction "PB5/AIN12/SPI_MOSI/T31_CH1/TX1/PINT7_9") (pintype "passive"))
    )
    (net (code "20") (name "/USB_IN") (class "Default")
      (node (ref "C9") (pin "2") (pinfunction "2_2") (pintype "passive"))
      (node (ref "CN2") (pin "1") (pinfunction "1_1") (pintype "passive"))
      (node (ref "R16") (pin "2") (pinfunction "2_2") (pintype "passive"))
      (node (ref "R20") (pin "1") (pinfunction "1_1") (pintype "passive"))
      (node (ref "R28") (pin "2") (pinfunction "2_2") (pintype "passive"))
    )
    (net (code "21") (name "/VBAT_IN") (class "Default")
      (node (ref "C6") (pin "2") (pinfunction "2_2") (pintype "passive"))
      (node (ref "R11") (pin "2") (pinfunction "2_2") (pintype "passive"))
      (node (ref "R7") (pin "1") (pinfunction "1_1") (pintype "passive"))
      (node (ref "U1") (pin "6") (pinfunction "PB2/AIN4/T31_CH1N/T11CKI/BEEPO/KIN3_6") (pintype "passive"))
    )
    (net (code "22") (name "GND") (class "Default")
      (node (ref "C1") (pin "2") (pinfunction "2_2") (pintype "passive"))
      (node (ref "C10") (pin "1") (pinfunction "1_1") (pintype "passive"))
      (node (ref "C11") (pin "1") (pinfunction "1_1") (pintype "passive"))
      (node (ref "C12") (pin "1") (pinfunction "1_1") (pintype "passive"))
      (node (ref "C13") (pin "2") (pinfunction "2_2") (pintype "passive"))
      (node (ref "C14") (pin "1") (pinfunction "1_1") (pintype "passive"))
      (node (ref "C2") (pin "1") (pinfunction "1_1") (pintype "passive"))
      (node (ref "C3") (pin "2") (pinfunction "2_2") (pintype "passive"))
      (node (ref "C4") (pin "2") (pinfunction "2_2") (pintype "passive"))
      (node (ref "C5") (pin "2") (pinfunction "2_2") (pintype "passive"))
      (node (ref "C6") (pin "1") (pinfunction "1_1") (pintype "passive"))
      (node (ref "C7") (pin "1") (pinfunction "1_1") (pintype "passive"))
      (node (ref "C8") (pin "2") (pinfunction "2_2") (pintype "passive"))
      (node (ref "C9") (pin "1") (pinfunction "1_1") (pintype "passive"))
      (node (ref "CN1") (pin "2") (pinfunction "2_2") (pintype "passive"))
      (node (ref "CN2") (pin "2") (pinfunction "2_2") (pintype "passive"))
      (node (ref "CN4") (pin "1") (pinfunction "1_1") (pintype "passive"))
      (node (ref "H1") (pin "5") (pinfunction "5_5") (pintype "passive"))
      (node (ref "Q1") (pin "2") (pinfunction "S_2") (pintype "passive"))
      (node (ref "Q3") (pin "2") (pinfunction "E_2") (pintype "passive"))
      (node (ref "R11") (pin "1") (pinfunction "1_1") (pintype "passive"))
      (node (ref "R12") (pin "1") (pinfunction "1_1") (pintype "passive"))
      (node (ref "R13") (pin "2") (pinfunction "2_2") (pintype "passive"))
      (node (ref "R222") (pin "2") (pinfunction "2_2") (pintype "passive"))
      (node (ref "R227") (pin "2") (pinfunction "2_2") (pintype "passive"))
      (node (ref "R24") (pin "2") (pinfunction "2_2") (pintype "passive"))
      (node (ref "R25") (pin "2") (pinfunction "2_2") (pintype "passive"))
      (node (ref "R34") (pin "1") (pinfunction "1_1") (pintype "passive"))
      (node (ref "R35") (pin "1") (pinfunction "1_1") (pintype "passive"))
      (node (ref "R9") (pin "1") (pinfunction "1_1") (pintype "passive"))
      (node (ref "U1") (pin "1") (pinfunction "VSS_1") (pintype "passive"))
      (node (ref "U2") (pin "2") (pinfunction "GND_2") (pintype "passive"))
      (node (ref "U3") (pin "2") (pinfunction "GND_2") (pintype "passive"))
    )
    (net (code "23") (name "Net-(BUZZER1-Pad2)") (class "Default")
      (node (ref "BUZZER1") (pin "2") (pinfunction "2_2") (pintype "passive"))
      (node (ref "R1") (pin "1") (pinfunction "1_1") (pintype "passive"))
    )
    (net (code "24") (name "Net-(C5-Pad1)") (class "Default")
      (node (ref "C5") (pin "1") (pinfunction "1_1") (pintype "passive"))
      (node (ref "J1") (pin "1") (pinfunction "1_1") (pintype "passive"))
      (node (ref "R8") (pin "2") (pinfunction "2_2") (pintype "passive"))
    )
    (net (code "25") (name "Net-(C10-Pad2)") (class "Default")
      (node (ref "C10") (pin "2") (pinfunction "2_2") (pintype "passive"))
      (node (ref "R26") (pin "1") (pinfunction "1_1") (pintype "passive"))
    )
    (net (code "26") (name "Net-(CN3-Pad1)") (class "Default")
      (node (ref "CN3") (pin "1") (pinfunction "1_1") (pintype "passive"))
      (node (ref "D2") (pin "1") (pinfunction "1_1") (pintype "passive"))
      (node (ref "L1") (pin "1") (pinfunction "1_1") (pintype "passive"))
      (node (ref "L2") (pin "1") (pinfunction "1_1") (pintype "passive"))
    )
    (net (code "27") (name "Net-(CN4-Pad2)") (class "Default")
      (node (ref "CN4") (pin "2") (pinfunction "2_2") (pintype "passive"))
      (node (ref "R30") (pin "2") (pinfunction "2_2") (pintype "passive"))
      (node (ref "R31") (pin "1") (pinfunction "1_1") (pintype "passive"))
    )
    (net (code "28") (name "Net-(D1-A)") (class "Default")
      (node (ref "D1") (pin "1") (pinfunction "A_1") (pintype "passive"))
      (node (ref "R14") (pin "1") (pinfunction "1_1") (pintype "passive"))
      (node (ref "R22") (pin "1") (pinfunction "1_1") (pintype "passive"))
    )
    (net (code "29") (name "Net-(D1-K)") (class "Default")
      (node (ref "D1") (pin "2") (pinfunction "K_2") (pintype "passive"))
      (node (ref "Q2") (pin "2") (pinfunction "S_2") (pintype "passive"))
      (node (ref "R18") (pin "1") (pinfunction "1_1") (pintype "passive"))
    )
    (net (code "30") (name "Net-(L3-Pad1)") (class "Default")
      (node (ref "L3") (pin "1") (pinfunction "1_1") (pintype "passive"))
      (node (ref "R15") (pin "1") (pinfunction "1_1") (pintype "passive"))
      (node (ref "R22") (pin "2") (pinfunction "2_2") (pintype "passive"))
      (node (ref "R23") (pin "2") (pinfunction "2_2") (pintype "passive"))
    )
    (net (code "31") (name "Net-(L3-Pad2)") (class "Default")
      (node (ref "L3") (pin "2") (pinfunction "2_2") (pintype "passive"))
      (node (ref "R20") (pin "2") (pinfunction "2_2") (pintype "passive"))
    )
    (net (code "32") (name "Net-(LED21-Pad1)") (class "Default")
      (node (ref "LED21") (pin "1") (pinfunction "1_1") (pintype "passive"))
      (node (ref "R17") (pin "2") (pinfunction "2_2") (pintype "passive"))
    )
    (net (code "33") (name "Net-(Q1-D)") (class "Default")
      (node (ref "Q1") (pin "3") (pinfunction "D_3") (pintype "passive"))
      (node (ref "R1") (pin "2") (pinfunction "2_2") (pintype "passive"))
    )
    (net (code "34") (name "Net-(Q1-G)") (class "Default")
      (node (ref "Q1") (pin "1") (pinfunction "G_1") (pintype "passive"))
      (node (ref "R2") (pin "1") (pinfunction "1_1") (pintype "passive"))
      (node (ref "R222") (pin "1") (pinfunction "1_1") (pintype "passive"))
    )
    (net (code "35") (name "Net-(Q2-G)") (class "Default")
      (node (ref "Q2") (pin "1") (pinfunction "G_1") (pintype "passive"))
      (node (ref "Q3") (pin "3") (pinfunction "C_3") (pintype "passive"))
      (node (ref "R23") (pin "1") (pinfunction "1_1") (pintype "passive"))
    )
    (net (code "36") (name "Net-(Q3-B)") (class "Default")
      (node (ref "Q3") (pin "1") (pinfunction "B_1") (pintype "passive"))
      (node (ref "R227") (pin "1") (pinfunction "1_1") (pintype "passive"))
      (node (ref "R27") (pin "1") (pinfunction "1_1") (pintype "passive"))
    )
    (net (code "37") (name "Net-(Q4-D)") (class "Default")
      (node (ref "CN3") (pin "2") (pinfunction "2_2") (pintype "passive"))
      (node (ref "D2") (pin "2") (pinfunction "2_2") (pintype "passive"))
      (node (ref "Q4") (pin "3") (pinfunction "D_3") (pintype "passive"))
      (node (ref "R26") (pin "2") (pinfunction "2_2") (pintype "passive"))
    )
    (net (code "38") (name "Net-(Q4-G)") (class "Default")
      (node (ref "Q4") (pin "1") (pinfunction "G_1") (pintype "passive"))
      (node (ref "R29") (pin "2") (pinfunction "2_2") (pintype "passive"))
    )
    (net (code "39") (name "Net-(Q4-S)") (class "Default")
      (node (ref "Q4") (pin "2") (pinfunction "S_2") (pintype "passive"))
      (node (ref "Q5") (pin "3") (pinfunction "D_3") (pintype "passive"))
    )
    (net (code "40") (name "Net-(Q5-G)") (class "Default")
      (node (ref "Q5") (pin "1") (pinfunction "G_1") (pintype "passive"))
      (node (ref "R32") (pin "2") (pinfunction "2_2") (pintype "passive"))
    )
    (net (code "41") (name "Net-(Q5-S)") (class "Default")
      (node (ref "Q5") (pin "2") (pinfunction "S_2") (pintype "passive"))
      (node (ref "R33") (pin "1") (pinfunction "1_1") (pintype "passive"))
      (node (ref "R34") (pin "2") (pinfunction "2_2") (pintype "passive"))
      (node (ref "R35") (pin "2") (pinfunction "2_2") (pintype "passive"))
    )
    (net (code "42") (name "Net-(R16-Pad1)") (class "Default")
      (node (ref "R16") (pin "1") (pinfunction "1_1") (pintype "passive"))
      (node (ref "R21") (pin "1") (pinfunction "1_1") (pintype "passive"))
      (node (ref "R25") (pin "1") (pinfunction "1_1") (pintype "passive"))
    )
    (net (code "43") (name "Net-(U2-C1)") (class "Default")
      (node (ref "C1") (pin "1") (pinfunction "1_1") (pintype "passive"))
      (node (ref "U2") (pin "6") (pinfunction "C1_6") (pintype "passive"))
    )
    (net (code "44") (name "Net-(U2-KEY)") (class "Default")
      (node (ref "R8") (pin "1") (pinfunction "1_1") (pintype "passive"))
      (node (ref "U2") (pin "3") (pinfunction "KEY_3") (pintype "passive"))
    )
    (net (code "45") (name "Net-(U2-MD)") (class "Default")
      (node (ref "R10") (pin "2") (pinfunction "2_2") (pintype "passive"))
      (node (ref "R9") (pin "2") (pinfunction "2_2") (pintype "passive"))
      (node (ref "U2") (pin "4") (pinfunction "MD_4") (pintype "passive"))
    )
    (net (code "46") (name "Net-(U2-VDD)") (class "Default")
      (node (ref "C2") (pin "2") (pinfunction "2_2") (pintype "passive"))
      (node (ref "R5") (pin "1") (pinfunction "1_1") (pintype "passive"))
      (node (ref "U2") (pin "5") (pinfunction "VDD_5") (pintype "passive"))
    )
    (net (code "47") (name "Net-(U3-CHRG)") (class "Default")
      (node (ref "LED21") (pin "2") (pinfunction "2_2") (pintype "passive"))
      (node (ref "U3") (pin "1") (pinfunction "CHRG_1") (pintype "passive"))
    )
    (net (code "48") (name "Net-(U3-PROG)") (class "Default")
      (node (ref "R24") (pin "1") (pinfunction "1_1") (pintype "passive"))
      (node (ref "U3") (pin "5") (pinfunction "PROG_5") (pintype "passive"))
    )
    (net (code "49") (name "Net-(U3-VCC)") (class "Default")
      (node (ref "C12") (pin "2") (pinfunction "2_2") (pintype "passive"))
      (node (ref "R17") (pin "1") (pinfunction "1_1") (pintype "passive"))
      (node (ref "R28") (pin "1") (pinfunction "1_1") (pintype "passive"))
      (node (ref "U3") (pin "4") (pinfunction "VCC_4") (pintype "passive"))
    )
    (net (code "50") (name "VBAT") (class "Default")
      (node (ref "BUZZER1") (pin "1") (pinfunction "1_1") (pintype "passive"))
      (node (ref "C11") (pin "2") (pinfunction "2_2") (pintype "passive"))
      (node (ref "C3") (pin "1") (pinfunction "1_1") (pintype "passive"))
      (node (ref "C4") (pin "1") (pinfunction "1_1") (pintype "passive"))
      (node (ref "CN1") (pin "1") (pinfunction "1_1") (pintype "passive"))
      (node (ref "H1") (pin "1") (pinfunction "1_1") (pintype "passive"))
      (node (ref "L1") (pin "2") (pinfunction "2_2") (pintype "passive"))
      (node (ref "L2") (pin "2") (pinfunction "2_2") (pintype "passive"))
      (node (ref "Q2") (pin "3") (pinfunction "D_3") (pintype "passive"))
      (node (ref "R10") (pin "1") (pinfunction "1_1") (pintype "passive"))
      (node (ref "R18") (pin "2") (pinfunction "2_2") (pintype "passive"))
      (node (ref "R5") (pin "2") (pinfunction "2_2") (pintype "passive"))
      (node (ref "R6") (pin "2") (pinfunction "2_2") (pintype "passive"))
      (node (ref "R7") (pin "2") (pinfunction "2_2") (pintype "passive"))
      (node (ref "U1") (pin "20") (pinfunction "VDD_20") (pintype "passive"))
      (node (ref "U3") (pin "3") (pinfunction "BAT_3") (pintype "passive"))
    )
  )
)
